# LcsNodes-Building-Block-Track-Sensor-2x4.net
KiCad netlist of a schematic drawn in EasyEDA
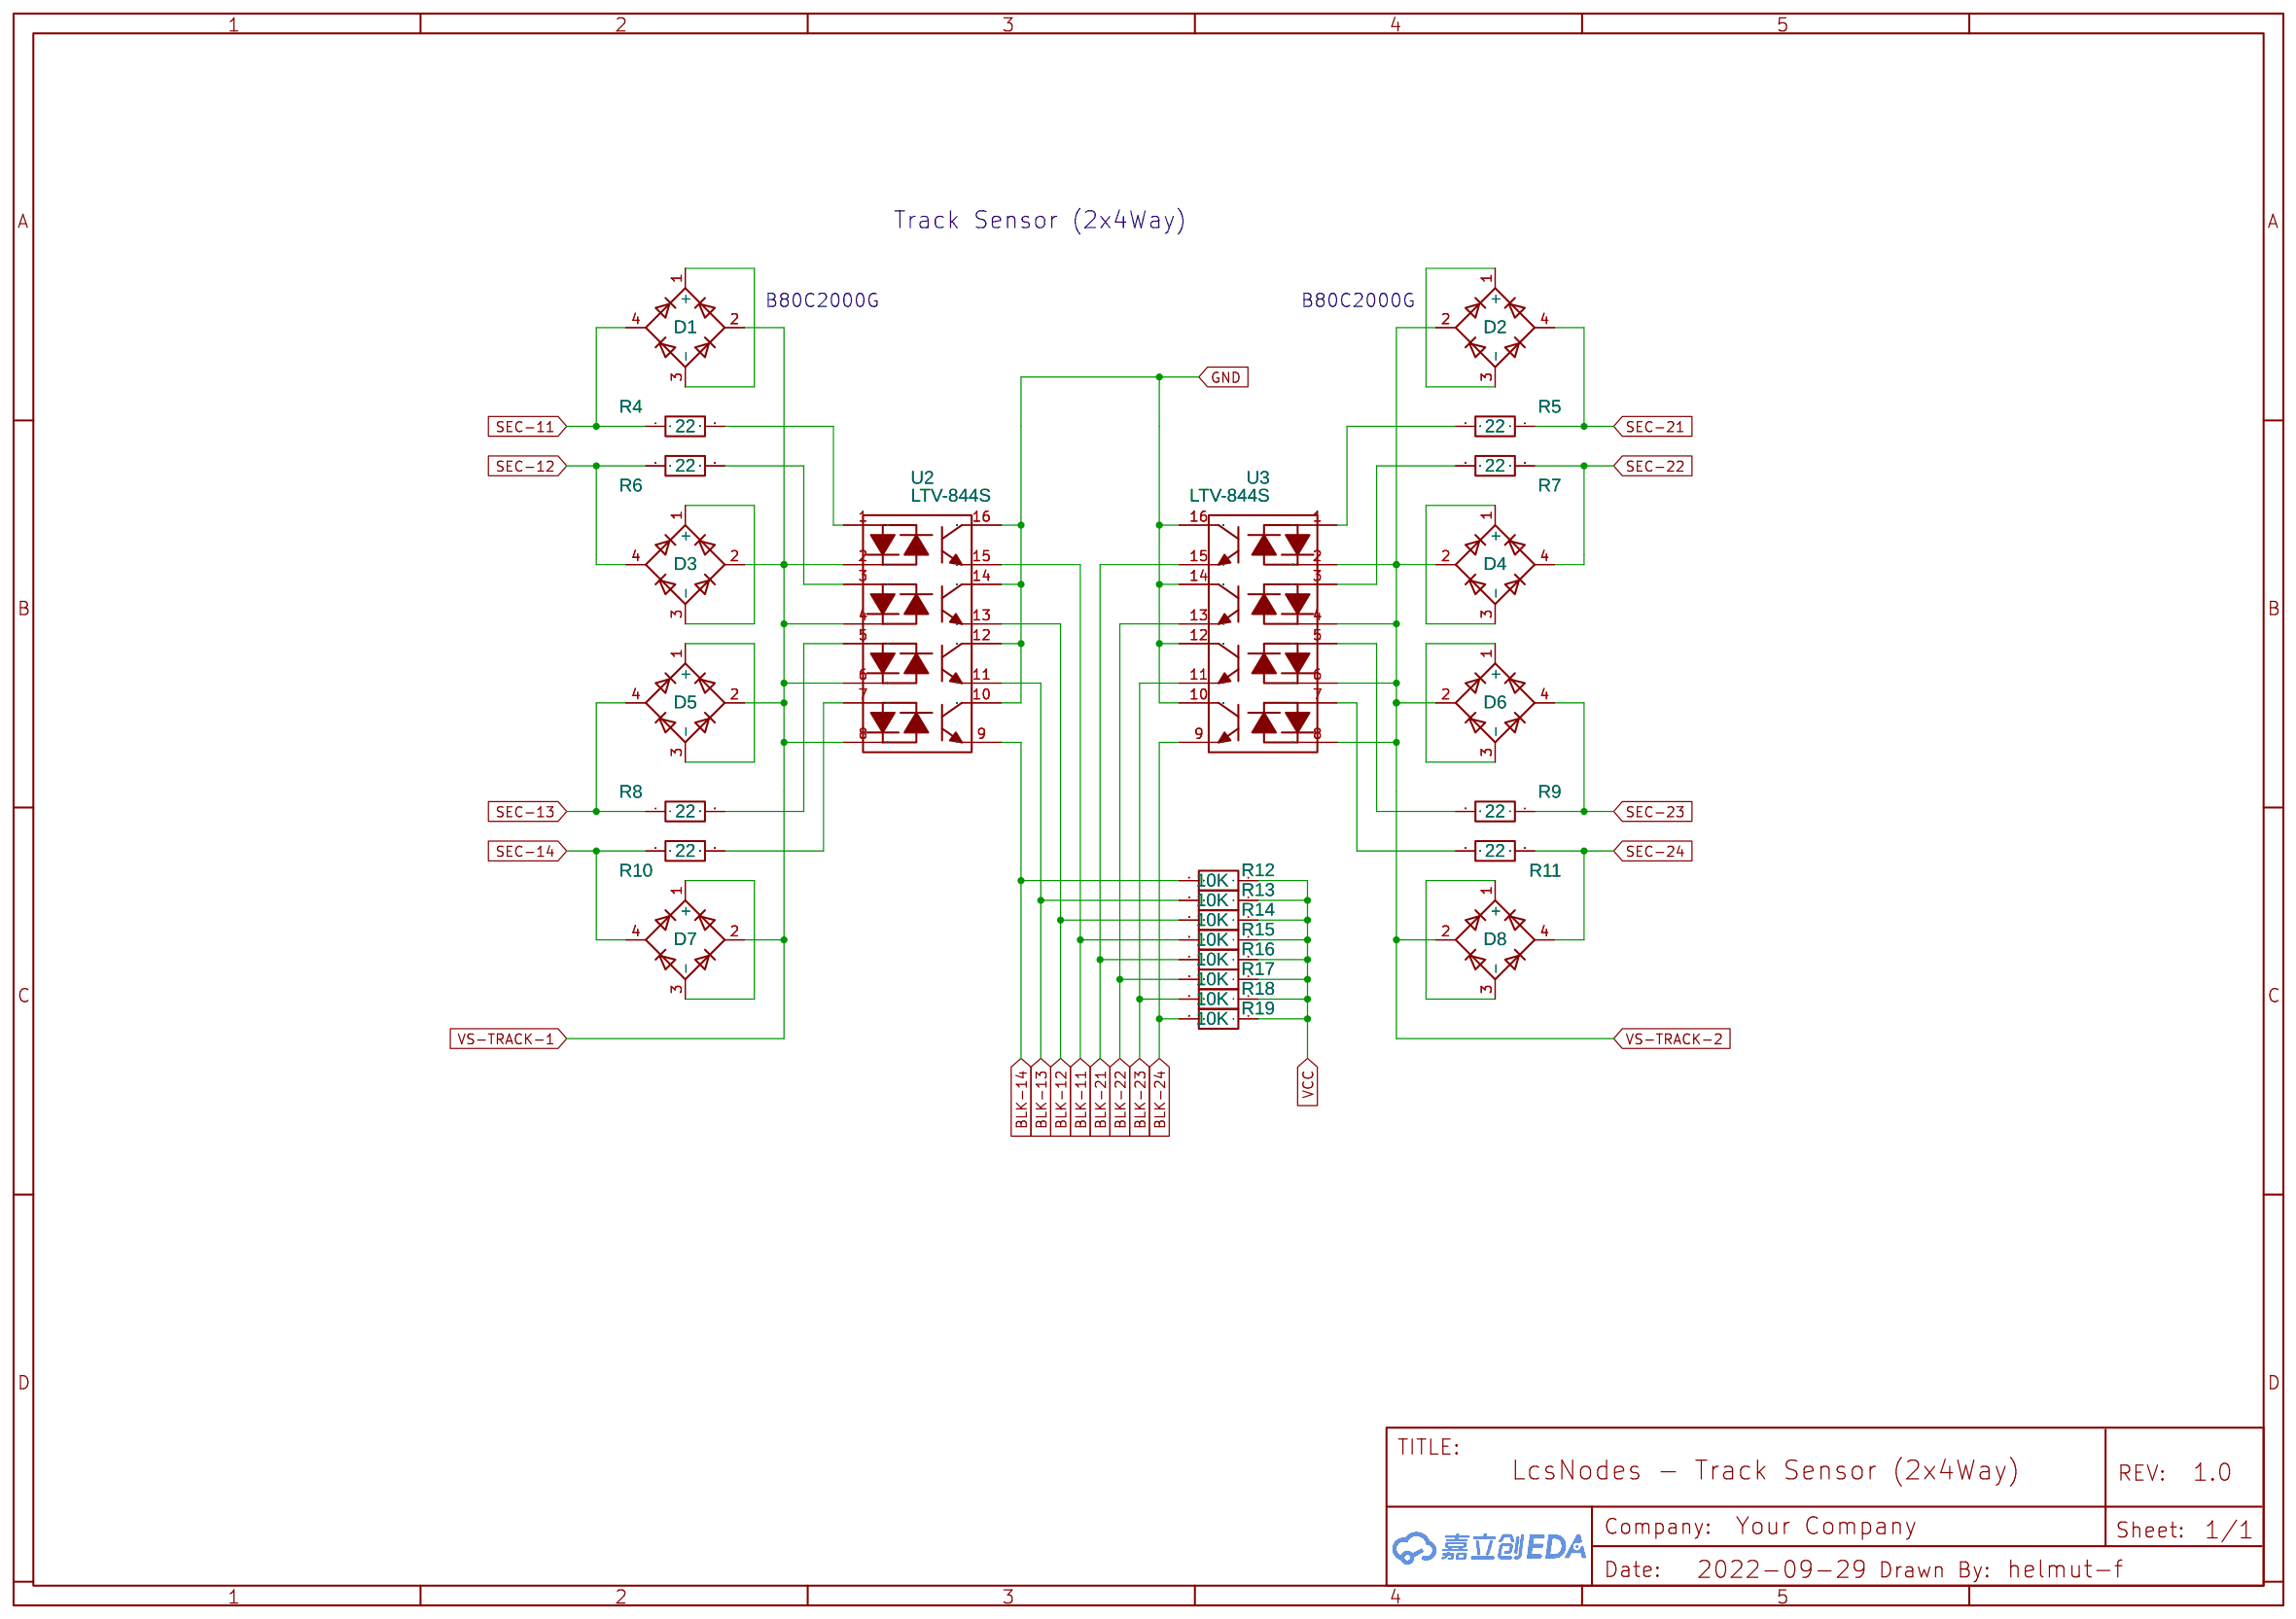
[diagram p0: schematic sheet]

(export (version "E")
  (design (tool "Eeschema 10.0.6"))
  (components
    (comp (ref "D1")
      (value "B80C2000G GLEICHRICHTER RUND")
      (libsource (lib "") (part "B80C1500G GLEICHRICHTER RUND_1"))
    )
    (comp (ref "D2")
      (value "B80C2000G GLEICHRICHTER RUND")
      (libsource (lib "") (part "B80C1500G GLEICHRICHTER RUND"))
    )
    (comp (ref "D3")
      (value "B80C2000G GLEICHRICHTER RUND")
      (libsource (lib "") (part "B80C1500G GLEICHRICHTER RUND_1"))
    )
    (comp (ref "D4")
      (value "B80C2000G GLEICHRICHTER RUND")
      (libsource (lib "") (part "B80C1500G GLEICHRICHTER RUND"))
    )
    (comp (ref "D5")
      (value "B80C2000G GLEICHRICHTER RUND")
      (libsource (lib "") (part "B80C1500G GLEICHRICHTER RUND_1"))
    )
    (comp (ref "D6")
      (value "B80C2000G GLEICHRICHTER RUND")
      (libsource (lib "") (part "B80C1500G GLEICHRICHTER RUND"))
    )
    (comp (ref "D7")
      (value "B80C2000G GLEICHRICHTER RUND")
      (libsource (lib "") (part "B80C1500G GLEICHRICHTER RUND_1"))
    )
    (comp (ref "D8")
      (value "B80C2000G GLEICHRICHTER RUND")
      (libsource (lib "") (part "B80C1500G GLEICHRICHTER RUND"))
    )
    (comp (ref "R4") (value "22") (libsource (lib "") (part "R_AXIAL-0.3_EU_1")))
    (comp (ref "R5") (value "22") (libsource (lib "") (part "R_AXIAL-0.3_EU")))
    (comp (ref "R6") (value "22") (libsource (lib "") (part "R_AXIAL-0.3_EU_1")))
    (comp (ref "R7") (value "22") (libsource (lib "") (part "R_AXIAL-0.3_EU")))
    (comp (ref "R8") (value "22") (libsource (lib "") (part "R_AXIAL-0.3_EU_1")))
    (comp (ref "R9") (value "22") (libsource (lib "") (part "R_AXIAL-0.3_EU")))
    (comp (ref "R10") (value "22") (libsource (lib "") (part "R_AXIAL-0.3_EU_1")))
    (comp (ref "R11") (value "22") (libsource (lib "") (part "R_AXIAL-0.3_EU")))
    (comp (ref "R12") (value "10K") (libsource (lib "") (part "R_AXIAL-0.3_EU")))
    (comp (ref "R13") (value "10K") (libsource (lib "") (part "R_AXIAL-0.3_EU")))
    (comp (ref "R14") (value "10K") (libsource (lib "") (part "R_AXIAL-0.3_EU")))
    (comp (ref "R15") (value "10K") (libsource (lib "") (part "R_AXIAL-0.3_EU")))
    (comp (ref "R16") (value "10K") (libsource (lib "") (part "R_AXIAL-0.3_EU")))
    (comp (ref "R17") (value "10K") (libsource (lib "") (part "R_AXIAL-0.3_EU")))
    (comp (ref "R18") (value "10K") (libsource (lib "") (part "R_AXIAL-0.3_EU")))
    (comp (ref "R19") (value "10K") (libsource (lib "") (part "R_AXIAL-0.3_EU")))
    (comp (ref "U2")
      (value "LTV-844S")
      (fields (field (name "BOM_Supplier Part") "C575506"))
      (libsource (lib "") (part "LTV-844S"))
    )
    (comp (ref "U3")
      (value "LTV-844S")
      (fields (field (name "BOM_Supplier Part") "C575506"))
      (libsource (lib "") (part "LTV-844S_1"))
    )
  )
  (nets
    (net (code "1") (name "BLK-11") (class "Default")
      (node (ref "R15") (pin "2") (pinfunction "2_2") (pintype "unspecified"))
      (node (ref "U2") (pin "15") (pinfunction "15_15") (pintype "unspecified"))
    )
    (net (code "2") (name "BLK-12") (class "Default")
      (node (ref "R14") (pin "2") (pinfunction "2_2") (pintype "unspecified"))
      (node (ref "U2") (pin "13") (pinfunction "13_13") (pintype "unspecified"))
    )
    (net (code "3") (name "BLK-13") (class "Default")
      (node (ref "R13") (pin "2") (pinfunction "2_2") (pintype "unspecified"))
      (node (ref "U2") (pin "11") (pinfunction "11_11") (pintype "unspecified"))
    )
    (net (code "4") (name "BLK-14") (class "Default")
      (node (ref "R12") (pin "2") (pinfunction "2_2") (pintype "unspecified"))
      (node (ref "U2") (pin "9") (pinfunction "9_9") (pintype "unspecified"))
    )
    (net (code "5") (name "BLK-21") (class "Default")
      (node (ref "R16") (pin "2") (pinfunction "2_2") (pintype "unspecified"))
      (node (ref "U3") (pin "15") (pinfunction "15_15") (pintype "unspecified"))
    )
    (net (code "6") (name "BLK-22") (class "Default")
      (node (ref "R17") (pin "2") (pinfunction "2_2") (pintype "unspecified"))
      (node (ref "U3") (pin "13") (pinfunction "13_13") (pintype "unspecified"))
    )
    (net (code "7") (name "BLK-23") (class "Default")
      (node (ref "R18") (pin "2") (pinfunction "2_2") (pintype "unspecified"))
      (node (ref "U3") (pin "11") (pinfunction "11_11") (pintype "unspecified"))
    )
    (net (code "8") (name "BLK-24") (class "Default")
      (node (ref "R19") (pin "2") (pinfunction "2_2") (pintype "unspecified"))
      (node (ref "U3") (pin "9") (pinfunction "9_9") (pintype "unspecified"))
    )
    (net (code "9") (name "GND") (class "Default")
      (node (ref "U2") (pin "10") (pinfunction "10_10") (pintype "unspecified"))
      (node (ref "U2") (pin "12") (pinfunction "12_12") (pintype "unspecified"))
      (node (ref "U2") (pin "14") (pinfunction "14_14") (pintype "unspecified"))
      (node (ref "U2") (pin "16") (pinfunction "16_16") (pintype "unspecified"))
      (node (ref "U3") (pin "10") (pinfunction "10_10") (pintype "unspecified"))
      (node (ref "U3") (pin "12") (pinfunction "12_12") (pintype "unspecified"))
      (node (ref "U3") (pin "14") (pinfunction "14_14") (pintype "unspecified"))
      (node (ref "U3") (pin "16") (pinfunction "16_16") (pintype "unspecified"))
    )
    (net (code "10") (name "Net-(D1-+)") (class "Default")
      (node (ref "D1") (pin "1") (pinfunction "+_1") (pintype "unspecified"))
      (node (ref "D1") (pin "3") (pinfunction "-_3") (pintype "unspecified"))
    )
    (net (code "11") (name "Net-(D2-+)") (class "Default")
      (node (ref "D2") (pin "1") (pinfunction "+_1") (pintype "unspecified"))
      (node (ref "D2") (pin "3") (pinfunction "-_3") (pintype "unspecified"))
    )
    (net (code "12") (name "Net-(D3-+)") (class "Default")
      (node (ref "D3") (pin "1") (pinfunction "+_1") (pintype "unspecified"))
      (node (ref "D3") (pin "3") (pinfunction "-_3") (pintype "unspecified"))
    )
    (net (code "13") (name "Net-(D4-+)") (class "Default")
      (node (ref "D4") (pin "1") (pinfunction "+_1") (pintype "unspecified"))
      (node (ref "D4") (pin "3") (pinfunction "-_3") (pintype "unspecified"))
    )
    (net (code "14") (name "Net-(D5-+)") (class "Default")
      (node (ref "D5") (pin "1") (pinfunction "+_1") (pintype "unspecified"))
      (node (ref "D5") (pin "3") (pinfunction "-_3") (pintype "unspecified"))
    )
    (net (code "15") (name "Net-(D6-+)") (class "Default")
      (node (ref "D6") (pin "1") (pinfunction "+_1") (pintype "unspecified"))
      (node (ref "D6") (pin "3") (pinfunction "-_3") (pintype "unspecified"))
    )
    (net (code "16") (name "Net-(D7-+)") (class "Default")
      (node (ref "D7") (pin "1") (pinfunction "+_1") (pintype "unspecified"))
      (node (ref "D7") (pin "3") (pinfunction "-_3") (pintype "unspecified"))
    )
    (net (code "17") (name "Net-(D8-+)") (class "Default")
      (node (ref "D8") (pin "1") (pinfunction "+_1") (pintype "unspecified"))
      (node (ref "D8") (pin "3") (pinfunction "-_3") (pintype "unspecified"))
    )
    (net (code "18") (name "Net-(R4-Pad2)") (class "Default")
      (node (ref "R4") (pin "2") (pinfunction "2_2") (pintype "unspecified"))
      (node (ref "U2") (pin "1") (pinfunction "1_1") (pintype "unspecified"))
    )
    (net (code "19") (name "Net-(R5-Pad2)") (class "Default")
      (node (ref "R5") (pin "2") (pinfunction "2_2") (pintype "unspecified"))
      (node (ref "U3") (pin "1") (pinfunction "1_1") (pintype "unspecified"))
    )
    (net (code "20") (name "Net-(R6-Pad2)") (class "Default")
      (node (ref "R6") (pin "2") (pinfunction "2_2") (pintype "unspecified"))
      (node (ref "U2") (pin "3") (pinfunction "3_3") (pintype "unspecified"))
    )
    (net (code "21") (name "Net-(R7-Pad2)") (class "Default")
      (node (ref "R7") (pin "2") (pinfunction "2_2") (pintype "unspecified"))
      (node (ref "U3") (pin "3") (pinfunction "3_3") (pintype "unspecified"))
    )
    (net (code "22") (name "Net-(R8-Pad2)") (class "Default")
      (node (ref "R8") (pin "2") (pinfunction "2_2") (pintype "unspecified"))
      (node (ref "U2") (pin "5") (pinfunction "5_5") (pintype "unspecified"))
    )
    (net (code "23") (name "Net-(R9-Pad2)") (class "Default")
      (node (ref "R9") (pin "2") (pinfunction "2_2") (pintype "unspecified"))
      (node (ref "U3") (pin "5") (pinfunction "5_5") (pintype "unspecified"))
    )
    (net (code "24") (name "Net-(R10-Pad2)") (class "Default")
      (node (ref "R10") (pin "2") (pinfunction "2_2") (pintype "unspecified"))
      (node (ref "U2") (pin "7") (pinfunction "7_7") (pintype "unspecified"))
    )
    (net (code "25") (name "Net-(R11-Pad2)") (class "Default")
      (node (ref "R11") (pin "2") (pinfunction "2_2") (pintype "unspecified"))
      (node (ref "U3") (pin "7") (pinfunction "7_7") (pintype "unspecified"))
    )
    (net (code "26") (name "SEC-11") (class "Default")
      (node (ref "D1") (pin "4") (pintype "unspecified"))
      (node (ref "R4") (pin "1") (pinfunction "1_1") (pintype "unspecified"))
    )
    (net (code "27") (name "SEC-12") (class "Default")
      (node (ref "D3") (pin "4") (pintype "unspecified"))
      (node (ref "R6") (pin "1") (pinfunction "1_1") (pintype "unspecified"))
    )
    (net (code "28") (name "SEC-13") (class "Default")
      (node (ref "D5") (pin "4") (pintype "unspecified"))
      (node (ref "R8") (pin "1") (pinfunction "1_1") (pintype "unspecified"))
    )
    (net (code "29") (name "SEC-14") (class "Default")
      (node (ref "D7") (pin "4") (pintype "unspecified"))
      (node (ref "R10") (pin "1") (pinfunction "1_1") (pintype "unspecified"))
    )
    (net (code "30") (name "SEC-21") (class "Default")
      (node (ref "D2") (pin "4") (pintype "unspecified"))
      (node (ref "R5") (pin "1") (pinfunction "1_1") (pintype "unspecified"))
    )
    (net (code "31") (name "SEC-22") (class "Default")
      (node (ref "D4") (pin "4") (pintype "unspecified"))
      (node (ref "R7") (pin "1") (pinfunction "1_1") (pintype "unspecified"))
    )
    (net (code "32") (name "SEC-23") (class "Default")
      (node (ref "D6") (pin "4") (pintype "unspecified"))
      (node (ref "R9") (pin "1") (pinfunction "1_1") (pintype "unspecified"))
    )
    (net (code "33") (name "SEC-24") (class "Default")
      (node (ref "D8") (pin "4") (pintype "unspecified"))
      (node (ref "R11") (pin "1") (pinfunction "1_1") (pintype "unspecified"))
    )
    (net (code "34") (name "VCC") (class "Default")
      (node (ref "R12") (pin "1") (pinfunction "1_1") (pintype "unspecified"))
      (node (ref "R13") (pin "1") (pinfunction "1_1") (pintype "unspecified"))
      (node (ref "R14") (pin "1") (pinfunction "1_1") (pintype "unspecified"))
      (node (ref "R15") (pin "1") (pinfunction "1_1") (pintype "unspecified"))
      (node (ref "R16") (pin "1") (pinfunction "1_1") (pintype "unspecified"))
      (node (ref "R17") (pin "1") (pinfunction "1_1") (pintype "unspecified"))
      (node (ref "R18") (pin "1") (pinfunction "1_1") (pintype "unspecified"))
      (node (ref "R19") (pin "1") (pinfunction "1_1") (pintype "unspecified"))
    )
    (net (code "35") (name "VS-TRACK-1") (class "Default")
      (node (ref "D1") (pin "2") (pintype "unspecified"))
      (node (ref "D3") (pin "2") (pintype "unspecified"))
      (node (ref "D5") (pin "2") (pintype "unspecified"))
      (node (ref "D7") (pin "2") (pintype "unspecified"))
      (node (ref "U2") (pin "2") (pinfunction "2_2") (pintype "unspecified"))
      (node (ref "U2") (pin "4") (pinfunction "4_4") (pintype "unspecified"))
      (node (ref "U2") (pin "6") (pinfunction "6_6") (pintype "unspecified"))
      (node (ref "U2") (pin "8") (pinfunction "8_8") (pintype "unspecified"))
    )
    (net (code "36") (name "VS-TRACK-2") (class "Default")
      (node (ref "D2") (pin "2") (pintype "unspecified"))
      (node (ref "D4") (pin "2") (pintype "unspecified"))
      (node (ref "D6") (pin "2") (pintype "unspecified"))
      (node (ref "D8") (pin "2") (pintype "unspecified"))
      (node (ref "U3") (pin "2") (pinfunction "2_2") (pintype "unspecified"))
      (node (ref "U3") (pin "4") (pinfunction "4_4") (pintype "unspecified"))
      (node (ref "U3") (pin "6") (pinfunction "6_6") (pintype "unspecified"))
      (node (ref "U3") (pin "8") (pinfunction "8_8") (pintype "unspecified"))
    )
  )
)
